# schematic_gprs.net
KiCad netlist of a schematic drawn in EAGLE
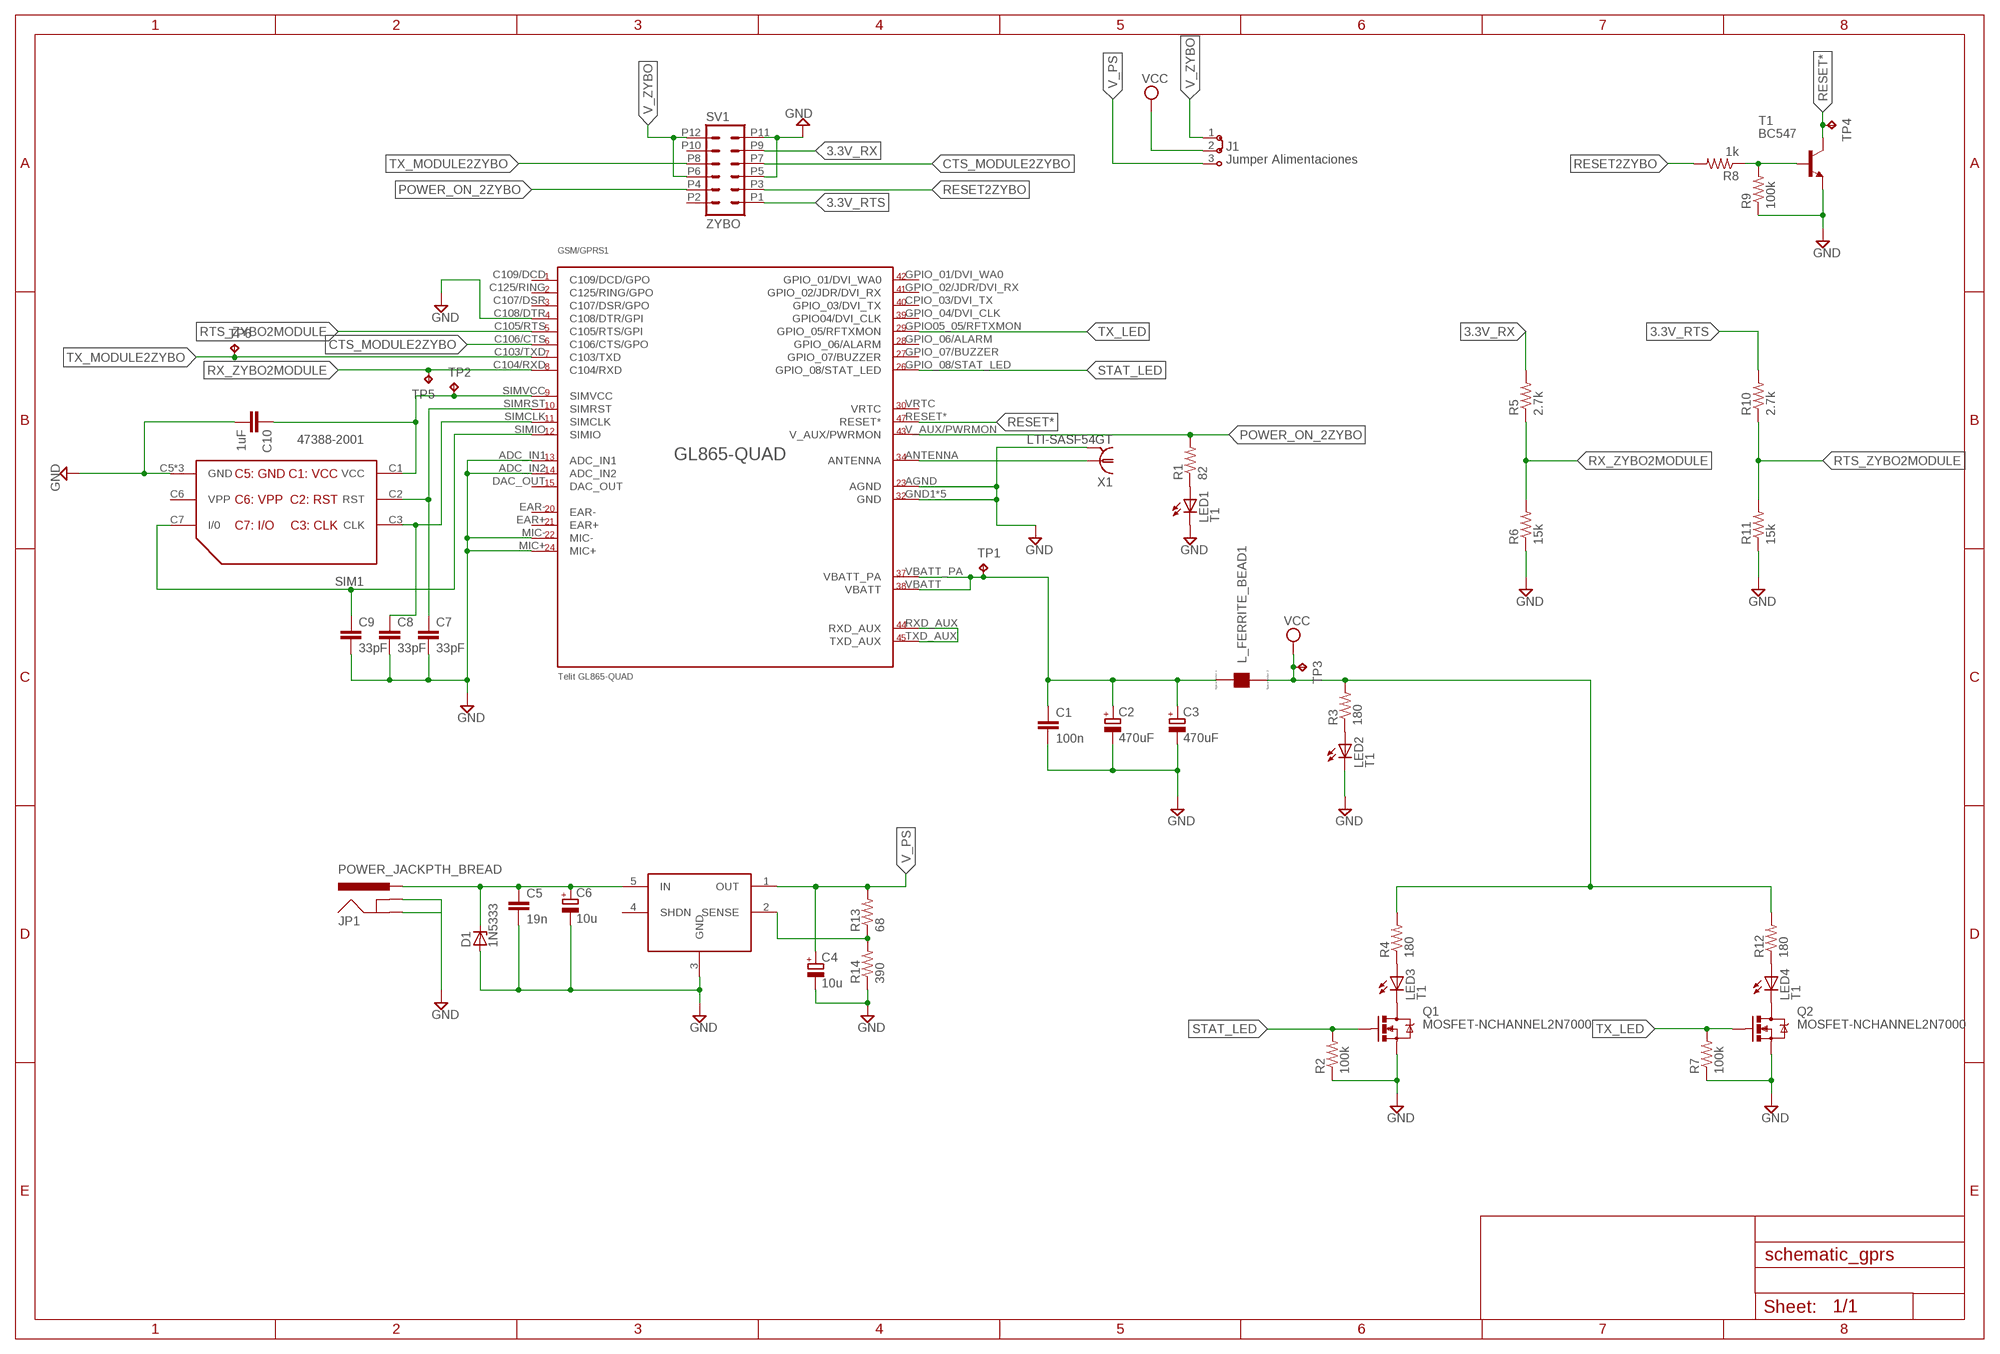
[diagram p0: schematic, sheet 1]

(export (version "E")
  (design (tool "Eeschema 10.0.6"))
  (components
    (comp (ref "C1")
      (value "100n")
      (footprint "eagle-import:C2.5-2")
      (libsource (lib "eagle-import") (part "C2.5/2"))
    )
    (comp (ref "C2")
      (value "470uF")
      (footprint "eagle-import:E3,5-8")
      (libsource (lib "eagle-import") (part "CPOL-EUE3.5-8"))
    )
    (comp (ref "C3")
      (value "470uF")
      (footprint "eagle-import:E3,5-8")
      (libsource (lib "eagle-import") (part "CPOL-EUE3.5-8"))
    )
    (comp (ref "C4")
      (value "10u")
      (footprint "eagle-import:E2-5")
      (libsource (lib "eagle-import") (part "CPOL-EUE2-5"))
    )
    (comp (ref "C5")
      (value "19n")
      (footprint "eagle-import:C050-025X075")
      (libsource (lib "eagle-import") (part "resistor_C-EU050-025X075"))
    )
    (comp (ref "C6")
      (value "10u")
      (footprint "eagle-import:E1,8-4")
      (libsource (lib "eagle-import") (part "CPOL-EUE1.8-4"))
    )
    (comp (ref "C7")
      (value "33pF")
      (footprint "eagle-import:C025-024X044")
      (libsource (lib "eagle-import") (part "C-EU025-024X044"))
    )
    (comp (ref "C8")
      (value "33pF")
      (footprint "eagle-import:C025-024X044")
      (libsource (lib "eagle-import") (part "C-EU025-024X044"))
    )
    (comp (ref "C9")
      (value "33pF")
      (footprint "eagle-import:C025-024X044")
      (libsource (lib "eagle-import") (part "C-EU025-024X044"))
    )
    (comp (ref "C10")
      (value "1uF")
      (footprint "eagle-import:CAP-PTH-SMALL-KIT")
      (libsource (lib "eagle-import") (part "CAPKIT"))
    )
    (comp (ref "D1")
      (value "1N5333")
      (footprint "eagle-import:C1702-15")
      (libsource (lib "eagle-import") (part "1N5333"))
    )
    (comp (ref "GSM/GPRS1")
      (value "Telit GL865-QUAD")
      (footprint "eagle-import:GL865-QUAD")
      (libsource (lib "eagle-import") (part "GL865-QUAD"))
    )
    (comp (ref "J1")
      (value "Jumper Alimentaciones")
      (footprint "eagle-import:04C")
      (libsource (lib "eagle-import") (part "J2X2MM"))
    )
    (comp (ref "JP1")
      (value "POWER_JACKPTH_BREAD")
      (footprint "eagle-import:POWER_JACK_PTH_BREAD")
      (libsource (lib "eagle-import") (part "POWER_JACKPTH_BREAD"))
    )
    (comp (ref "LED1")
      (value "T1")
      (footprint "eagle-import:LED3MM")
      (libsource (lib "eagle-import") (part "LED3MM"))
    )
    (comp (ref "LED2")
      (value "T1")
      (footprint "eagle-import:LED3MM")
      (libsource (lib "eagle-import") (part "LED3MM"))
    )
    (comp (ref "LED3")
      (value "T1")
      (footprint "eagle-import:LED3MM")
      (libsource (lib "eagle-import") (part "LED3MM"))
    )
    (comp (ref "LED4")
      (value "T1")
      (footprint "eagle-import:LED3MM")
      (libsource (lib "eagle-import") (part "LED3MM"))
    )
    (comp (ref "L_FERRITE_BEAD1")
      (value "FERRITEBEAD2")
      (footprint "eagle-import:0207_7")
      (libsource (lib "eagle-import") (part "FERRITEBEAD2"))
    )
    (comp (ref "Q1")
      (value "MOSFET-NCHANNEL2N7000")
      (footprint "eagle-import:TO-92")
      (libsource (lib "eagle-import") (part "MOSFET-NCHANNEL2N7000"))
    )
    (comp (ref "Q2")
      (value "MOSFET-NCHANNEL2N7000")
      (footprint "eagle-import:TO-92")
      (libsource (lib "eagle-import") (part "MOSFET-NCHANNEL2N7000"))
    )
    (comp (ref "R1")
      (value "82")
      (footprint "eagle-import:0207_7")
      (libsource (lib "eagle-import") (part "R-US_0207/7"))
    )
    (comp (ref "R2")
      (value "100k")
      (footprint "eagle-import:0207_7")
      (libsource (lib "eagle-import") (part "R-US_0207/7"))
    )
    (comp (ref "R3")
      (value "180")
      (footprint "eagle-import:0207_7")
      (libsource (lib "eagle-import") (part "R-US_0207/7"))
    )
    (comp (ref "R4")
      (value "180")
      (footprint "eagle-import:0207_7")
      (libsource (lib "eagle-import") (part "R-US_0207/7"))
    )
    (comp (ref "R5")
      (value "2.7k")
      (footprint "eagle-import:0207_7")
      (libsource (lib "eagle-import") (part "R-US_0207/7"))
    )
    (comp (ref "R6")
      (value "15k")
      (footprint "eagle-import:0207_7")
      (libsource (lib "eagle-import") (part "R-US_0207/7"))
    )
    (comp (ref "R7")
      (value "100k")
      (footprint "eagle-import:0207_7")
      (libsource (lib "eagle-import") (part "R-US_0207/7"))
    )
    (comp (ref "R8")
      (value "1k")
      (footprint "eagle-import:0207_7")
      (libsource (lib "eagle-import") (part "R-US_0207/7"))
    )
    (comp (ref "R9")
      (value "100k")
      (footprint "eagle-import:0207_7")
      (libsource (lib "eagle-import") (part "R-US_0207/7"))
    )
    (comp (ref "R10")
      (value "2.7k")
      (footprint "eagle-import:0207_7")
      (libsource (lib "eagle-import") (part "R-US_0207/7"))
    )
    (comp (ref "R11")
      (value "15k")
      (footprint "eagle-import:0207_7")
      (libsource (lib "eagle-import") (part "R-US_0207/7"))
    )
    (comp (ref "R12")
      (value "180")
      (footprint "eagle-import:0207_7")
      (libsource (lib "eagle-import") (part "R-US_0207/7"))
    )
    (comp (ref "R13")
      (value "68")
      (footprint "eagle-import:0207_7")
      (libsource (lib "eagle-import") (part "R-US_0207/7"))
    )
    (comp (ref "R14")
      (value "390")
      (footprint "eagle-import:0207_7")
      (libsource (lib "eagle-import") (part "R-US_0207/7"))
    )
    (comp (ref "SIM1")
      (value "47388-2001")
      (footprint "eagle-import:47388-2001")
      (libsource (lib "eagle-import") (part "47388-2001"))
    )
    (comp (ref "SV1")
      (value "ZYBO")
      (footprint "eagle-import:MA06-2")
      (libsource (lib "eagle-import") (part "MA06-2"))
    )
    (comp (ref "T1")
      (value "BC547")
      (footprint "eagle-import:TO92")
      (libsource (lib "eagle-import") (part "BC547"))
    )
    (comp (ref "TP1")
      (value "TPPAD1-13")
      (footprint "eagle-import:P1-13")
      (libsource (lib "eagle-import") (part "TPPAD1-13"))
    )
    (comp (ref "TP2")
      (value "TPPAD1-13")
      (footprint "eagle-import:P1-13")
      (libsource (lib "eagle-import") (part "TPPAD1-13"))
    )
    (comp (ref "TP3")
      (value "TPPAD1-13")
      (footprint "eagle-import:P1-13")
      (libsource (lib "eagle-import") (part "TPPAD1-13"))
    )
    (comp (ref "TP4")
      (value "TPPAD1-13")
      (footprint "eagle-import:P1-13")
      (libsource (lib "eagle-import") (part "TPPAD1-13"))
    )
    (comp (ref "TP5")
      (value "TPPAD1-13")
      (footprint "eagle-import:P1-13")
      (libsource (lib "eagle-import") (part "TPPAD1-13"))
    )
    (comp (ref "TP6")
      (value "TPPAD1-13")
      (footprint "eagle-import:P1-13")
      (libsource (lib "eagle-import") (part "TPPAD1-13"))
    )
    (comp (ref "U$1")
      (value "LT1528")
      (footprint "eagle-import:Q5-DD")
      (libsource (lib "eagle-import") (part "LT1528"))
    )
    (comp (ref "X1")
      (value "LTI-SASF54GT")
      (footprint "eagle-import:LTI-SASF54GT")
      (libsource (lib "eagle-import") (part "LTI-SASF54GT"))
    )
  )
  (nets
    (net (code "1") (name "3.3V_RTS") (class "Default")
      (node (ref "R10") (pin "2") (pinfunction "2_2") (pintype "passive"))
      (node (ref "SV1") (pin "P1") (pinfunction "1_P1") (pintype "passive"))
    )
    (net (code "2") (name "3.3V_RX") (class "Default")
      (node (ref "R5") (pin "2") (pinfunction "2_2") (pintype "passive"))
      (node (ref "SV1") (pin "P9") (pinfunction "9_P9") (pintype "passive"))
    )
    (net (code "3") (name "CTS_MODULE2ZYBO") (class "Default")
      (node (ref "GSM/GPRS1") (pin "C106/CTS") (pinfunction "C106/CTS/GPO_C106/CTS") (pintype "output"))
      (node (ref "SV1") (pin "P7") (pinfunction "7_P7") (pintype "passive"))
    )
    (net (code "4") (name "GND") (class "Default")
      (node (ref "C1") (pin "2") (pinfunction "2_2") (pintype "passive"))
      (node (ref "C10") (pin "2") (pinfunction "2_2") (pintype "passive"))
      (node (ref "C2") (pin "-") (pinfunction "-_-") (pintype "passive"))
      (node (ref "C3") (pin "-") (pinfunction "-_-") (pintype "passive"))
      (node (ref "C4") (pin "-") (pinfunction "-_-") (pintype "passive"))
      (node (ref "C5") (pin "2") (pinfunction "2_2") (pintype "passive"))
      (node (ref "C6") (pin "-") (pinfunction "-_-") (pintype "passive"))
      (node (ref "C7") (pin "2") (pinfunction "2_2") (pintype "passive"))
      (node (ref "C8") (pin "2") (pinfunction "2_2") (pintype "passive"))
      (node (ref "C9") (pin "2") (pinfunction "2_2") (pintype "passive"))
      (node (ref "D1") (pin "A") (pinfunction "A_A") (pintype "passive"))
      (node (ref "GSM/GPRS1") (pin "ADC_IN1") (pinfunction "ADC_IN1_ADC_IN1") (pintype "input"))
      (node (ref "GSM/GPRS1") (pin "ADC_IN2") (pinfunction "ADC_IN2_ADC_IN2") (pintype "input"))
      (node (ref "GSM/GPRS1") (pin "AGND") (pinfunction "AGND_AGND") (pintype "power_in"))
      (node (ref "GSM/GPRS1") (pin "C108/DTR") (pinfunction "C108/DTR/GPI_C108/DTR") (pintype "input"))
      (node (ref "GSM/GPRS1") (pin "GND1") (pinfunction "GND_GND1") (pintype "power_in"))
      (node (ref "GSM/GPRS1") (pin "GND2") (pinfunction "GND_GND2") (pintype "power_in"))
      (node (ref "GSM/GPRS1") (pin "GND3") (pinfunction "GND_GND3") (pintype "power_in"))
      (node (ref "GSM/GPRS1") (pin "GND4") (pinfunction "GND_GND4") (pintype "power_in"))
      (node (ref "GSM/GPRS1") (pin "GND5") (pinfunction "GND_GND5") (pintype "power_in"))
      (node (ref "GSM/GPRS1") (pin "MIC+") (pinfunction "MIC+_MIC+") (pintype "input"))
      (node (ref "GSM/GPRS1") (pin "MIC-") (pinfunction "MIC-_MIC-") (pintype "input"))
      (node (ref "JP1") (pin "GND") (pinfunction "GND_GND") (pintype "bidirectional"))
      (node (ref "JP1") (pin "GNDBREAK") (pinfunction "GNDBREAK_GNDBREAK") (pintype "bidirectional"))
      (node (ref "LED1") (pin "K") (pinfunction "C_K") (pintype "passive"))
      (node (ref "LED2") (pin "K") (pinfunction "C_K") (pintype "passive"))
      (node (ref "Q1") (pin "1") (pinfunction "S_1") (pintype "passive"))
      (node (ref "Q2") (pin "1") (pinfunction "S_1") (pintype "passive"))
      (node (ref "R11") (pin "1") (pinfunction "1_1") (pintype "passive"))
      (node (ref "R14") (pin "1") (pinfunction "1_1") (pintype "passive"))
      (node (ref "R2") (pin "1") (pinfunction "1_1") (pintype "passive"))
      (node (ref "R6") (pin "1") (pinfunction "1_1") (pintype "passive"))
      (node (ref "R7") (pin "1") (pinfunction "1_1") (pintype "passive"))
      (node (ref "R9") (pin "1") (pinfunction "1_1") (pintype "passive"))
      (node (ref "SIM1") (pin "C5") (pinfunction "GND_C5") (pintype "power_in"))
      (node (ref "SIM1") (pin "GND1") (pinfunction "GND_GND1") (pintype "power_in"))
      (node (ref "SIM1") (pin "GND2") (pinfunction "GND_GND2") (pintype "power_in"))
      (node (ref "SV1") (pin "P11") (pinfunction "11_P11") (pintype "passive"))
      (node (ref "SV1") (pin "P5") (pinfunction "5_P5") (pintype "passive"))
      (node (ref "T1") (pin "1") (pinfunction "E_1") (pintype "passive"))
      (node (ref "U$1") (pin "3") (pinfunction "GND_3") (pintype "bidirectional"))
      (node (ref "X1") (pin "2") (pinfunction "2_2") (pintype "passive"))
      (node (ref "X1") (pin "3") (pinfunction "2_3") (pintype "passive"))
      (node (ref "X1") (pin "4") (pinfunction "2_4") (pintype "passive"))
      (node (ref "X1") (pin "5") (pinfunction "2_5") (pintype "passive"))
    )
    (net (code "5") (name "Net-(GSM/GPRS1-PadANTENNA)") (class "Default")
      (node (ref "GSM/GPRS1") (pin "ANTENNA") (pinfunction "ANTENNA_ANTENNA") (pintype "output"))
      (node (ref "X1") (pin "1") (pinfunction "1_1") (pintype "passive"))
    )
    (net (code "6") (name "Net-(GSM/GPRS1-PadRXD_AUX)") (class "Default")
      (node (ref "GSM/GPRS1") (pin "RXD_AUX") (pinfunction "RXD_AUX_RXD_AUX") (pintype "input"))
      (node (ref "GSM/GPRS1") (pin "TXD_AUX") (pinfunction "TXD_AUX_TXD_AUX") (pintype "output"))
    )
    (net (code "7") (name "Net-(LED1-PadA)") (class "Default")
      (node (ref "LED1") (pin "A") (pinfunction "A_A") (pintype "passive"))
      (node (ref "R1") (pin "1") (pinfunction "1_1") (pintype "passive"))
    )
    (net (code "8") (name "Net-(LED2-PadA)") (class "Default")
      (node (ref "LED2") (pin "A") (pinfunction "A_A") (pintype "passive"))
      (node (ref "R3") (pin "1") (pinfunction "1_1") (pintype "passive"))
    )
    (net (code "9") (name "Net-(LED3-C)") (class "Default")
      (node (ref "LED3") (pin "K") (pinfunction "C_K") (pintype "passive"))
      (node (ref "Q1") (pin "3") (pinfunction "D_3") (pintype "passive"))
    )
    (net (code "10") (name "Net-(LED3-PadA)") (class "Default")
      (node (ref "LED3") (pin "A") (pinfunction "A_A") (pintype "passive"))
      (node (ref "R4") (pin "1") (pinfunction "1_1") (pintype "passive"))
    )
    (net (code "11") (name "Net-(LED4-C)") (class "Default")
      (node (ref "LED4") (pin "K") (pinfunction "C_K") (pintype "passive"))
      (node (ref "Q2") (pin "3") (pinfunction "D_3") (pintype "passive"))
    )
    (net (code "12") (name "Net-(LED4-PadA)") (class "Default")
      (node (ref "LED4") (pin "A") (pinfunction "A_A") (pintype "passive"))
      (node (ref "R12") (pin "1") (pinfunction "1_1") (pintype "passive"))
    )
    (net (code "13") (name "Net-(L_FERRITE_BEAD1-A)") (class "Default")
      (node (ref "C1") (pin "1") (pinfunction "1_1") (pintype "passive"))
      (node (ref "C2") (pin "+") (pinfunction "+_+") (pintype "passive"))
      (node (ref "C3") (pin "+") (pinfunction "+_+") (pintype "passive"))
      (node (ref "GSM/GPRS1") (pin "VBATT") (pinfunction "VBATT_VBATT") (pintype "power_in"))
      (node (ref "GSM/GPRS1") (pin "VBATT_PA") (pinfunction "VBATT_PA_VBATT_PA") (pintype "power_in"))
      (node (ref "L_FERRITE_BEAD1") (pin "1") (pinfunction "A_1") (pintype "passive"))
      (node (ref "TP1") (pin "TP") (pinfunction "TP_TP") (pintype "input"))
    )
    (net (code "14") (name "Net-(SIM1-CLK)") (class "Default")
      (node (ref "C8") (pin "1") (pinfunction "1_1") (pintype "passive"))
      (node (ref "GSM/GPRS1") (pin "SIMCLK") (pinfunction "SIMCLK_SIMCLK") (pintype "output"))
      (node (ref "SIM1") (pin "C3") (pinfunction "CLK_C3") (pintype "input"))
    )
    (net (code "15") (name "Net-(SIM1-I{slash}0)") (class "Default")
      (node (ref "C9") (pin "1") (pinfunction "1_1") (pintype "passive"))
      (node (ref "GSM/GPRS1") (pin "SIMIO") (pinfunction "SIMIO_SIMIO") (pintype "bidirectional"))
      (node (ref "SIM1") (pin "C7") (pinfunction "I/0_C7") (pintype "bidirectional"))
    )
    (net (code "16") (name "Net-(SIM1-RST)") (class "Default")
      (node (ref "C7") (pin "1") (pinfunction "1_1") (pintype "passive"))
      (node (ref "GSM/GPRS1") (pin "SIMRST") (pinfunction "SIMRST_SIMRST") (pintype "output"))
      (node (ref "SIM1") (pin "C2") (pinfunction "RST_C2") (pintype "input"))
    )
    (net (code "17") (name "Net-(SIM1-VCC)") (class "Default")
      (node (ref "C10") (pin "1") (pinfunction "1_1") (pintype "passive"))
      (node (ref "GSM/GPRS1") (pin "SIMVCC") (pinfunction "SIMVCC_SIMVCC") (pintype "power_in"))
      (node (ref "SIM1") (pin "C1") (pinfunction "VCC_C1") (pintype "power_in"))
      (node (ref "TP2") (pin "TP") (pinfunction "TP_TP") (pintype "input"))
    )
    (net (code "18") (name "Net-(T1-B)") (class "Default")
      (node (ref "R8") (pin "1") (pinfunction "1_1") (pintype "passive"))
      (node (ref "R9") (pin "2") (pinfunction "2_2") (pintype "passive"))
      (node (ref "T1") (pin "2") (pinfunction "B_2") (pintype "passive"))
    )
    (net (code "19") (name "Net-(U$1-IN)") (class "Default")
      (node (ref "C5") (pin "1") (pinfunction "1_1") (pintype "passive"))
      (node (ref "C6") (pin "+") (pinfunction "+_+") (pintype "passive"))
      (node (ref "D1") (pin "C") (pinfunction "C_C") (pintype "passive"))
      (node (ref "JP1") (pin "PWR") (pinfunction "PWR_PWR") (pintype "bidirectional"))
      (node (ref "U$1") (pin "5") (pinfunction "IN_5") (pintype "bidirectional"))
    )
    (net (code "20") (name "Net-(U$1-SENSE)") (class "Default")
      (node (ref "R13") (pin "1") (pinfunction "1_1") (pintype "passive"))
      (node (ref "R14") (pin "2") (pinfunction "2_2") (pintype "passive"))
      (node (ref "U$1") (pin "2") (pinfunction "SENSE_2") (pintype "bidirectional"))
    )
    (net (code "21") (name "POWER_ON_2ZYBO") (class "Default")
      (node (ref "GSM/GPRS1") (pin "V_AUX/PWRMON") (pinfunction "V_AUX/PWRMON_V_AUX/PWRMON") (pintype "output"))
      (node (ref "R1") (pin "2") (pinfunction "2_2") (pintype "passive"))
      (node (ref "SV1") (pin "P4") (pinfunction "4_P4") (pintype "passive"))
    )
    (net (code "22") (name "RESET*") (class "Default")
      (node (ref "GSM/GPRS1") (pin "RESET*") (pinfunction "RESET*_RESET*") (pintype "input"))
      (node (ref "T1") (pin "3") (pinfunction "C_3") (pintype "passive"))
      (node (ref "TP4") (pin "TP") (pinfunction "TP_TP") (pintype "input"))
    )
    (net (code "23") (name "RESET2ZYBO") (class "Default")
      (node (ref "R8") (pin "2") (pinfunction "2_2") (pintype "passive"))
      (node (ref "SV1") (pin "P3") (pinfunction "3_P3") (pintype "passive"))
    )
    (net (code "24") (name "RTS_ZYBO2MODULE") (class "Default")
      (node (ref "GSM/GPRS1") (pin "C105/RTS") (pinfunction "C105/RTS/GPI_C105/RTS") (pintype "input"))
      (node (ref "R10") (pin "1") (pinfunction "1_1") (pintype "passive"))
      (node (ref "R11") (pin "2") (pinfunction "2_2") (pintype "passive"))
    )
    (net (code "25") (name "RX_ZYBO2MODULE") (class "Default")
      (node (ref "GSM/GPRS1") (pin "C104/RXD") (pinfunction "C104/RXD_C104/RXD") (pintype "output"))
      (node (ref "R5") (pin "1") (pinfunction "1_1") (pintype "passive"))
      (node (ref "R6") (pin "2") (pinfunction "2_2") (pintype "passive"))
      (node (ref "TP5") (pin "TP") (pinfunction "TP_TP") (pintype "input"))
    )
    (net (code "26") (name "STAT_LED") (class "Default")
      (node (ref "GSM/GPRS1") (pin "GPIO_08/STAT_LED") (pinfunction "GPIO_08/STAT_LED_GPIO_08/STAT_LED") (pintype "bidirectional"))
      (node (ref "Q1") (pin "2") (pinfunction "G_2") (pintype "passive"))
      (node (ref "R2") (pin "2") (pinfunction "2_2") (pintype "passive"))
    )
    (net (code "27") (name "TX_LED") (class "Default")
      (node (ref "GSM/GPRS1") (pin "GPIO05_05/RFTXMON") (pinfunction "GPIO_05/RFTXMON_GPIO05_05/RFTXMON") (pintype "bidirectional"))
      (node (ref "Q2") (pin "2") (pinfunction "G_2") (pintype "passive"))
      (node (ref "R7") (pin "2") (pinfunction "2_2") (pintype "passive"))
    )
    (net (code "28") (name "TX_MODULE2ZYBO") (class "Default")
      (node (ref "GSM/GPRS1") (pin "C103/TXD") (pinfunction "C103/TXD_C103/TXD") (pintype "input"))
      (node (ref "SV1") (pin "P8") (pinfunction "8_P8") (pintype "passive"))
      (node (ref "TP6") (pin "TP") (pinfunction "TP_TP") (pintype "input"))
    )
    (net (code "29") (name "VCC") (class "Default")
      (node (ref "J1") (pin "2") (pinfunction "2_2") (pintype "passive"))
      (node (ref "L_FERRITE_BEAD1") (pin "2") (pinfunction "B_2") (pintype "passive"))
      (node (ref "R12") (pin "2") (pinfunction "2_2") (pintype "passive"))
      (node (ref "R3") (pin "2") (pinfunction "2_2") (pintype "passive"))
      (node (ref "R4") (pin "2") (pinfunction "2_2") (pintype "passive"))
      (node (ref "TP3") (pin "TP") (pinfunction "TP_TP") (pintype "input"))
    )
    (net (code "30") (name "V_PS") (class "Default")
      (node (ref "C4") (pin "+") (pinfunction "+_+") (pintype "passive"))
      (node (ref "J1") (pin "3") (pinfunction "3_3") (pintype "passive"))
      (node (ref "R13") (pin "2") (pinfunction "2_2") (pintype "passive"))
      (node (ref "U$1") (pin "1") (pinfunction "OUT_1") (pintype "bidirectional"))
    )
    (net (code "31") (name "V_ZYBO") (class "Default")
      (node (ref "J1") (pin "1") (pinfunction "1_1") (pintype "passive"))
      (node (ref "SV1") (pin "P12") (pinfunction "12_P12") (pintype "passive"))
      (node (ref "SV1") (pin "P6") (pinfunction "6_P6") (pintype "passive"))
    )
    (net (code "32") (name "unconnected-(GSM/GPRS1-C107{slash}DSR{slash}GPO-PadC107{slash}DSR)") (class "Default")
      (node (ref "GSM/GPRS1") (pin "C107/DSR") (pinfunction "C107/DSR/GPO_C107/DSR") (pintype "output"))
    )
    (net (code "33") (name "unconnected-(GSM/GPRS1-C109{slash}DCD{slash}GPO-PadC109{slash}DCD)") (class "Default")
      (node (ref "GSM/GPRS1") (pin "C109/DCD") (pinfunction "C109/DCD/GPO_C109/DCD") (pintype "output"))
    )
    (net (code "34") (name "unconnected-(GSM/GPRS1-C125{slash}RING{slash}GPO-PadC125{slash}RING)") (class "Default")
      (node (ref "GSM/GPRS1") (pin "C125/RING") (pinfunction "C125/RING/GPO_C125/RING") (pintype "output"))
    )
    (net (code "35") (name "unconnected-(GSM/GPRS1-GPIO04{slash}DVI_CLK-PadGPIO_04{slash}DVI_CLK)") (class "Default")
      (node (ref "GSM/GPRS1") (pin "GPIO_04/DVI_CLK") (pinfunction "GPIO04/DVI_CLK_GPIO_04/DVI_CLK") (pintype "bidirectional"))
    )
    (net (code "36") (name "unconnected-(GSM/GPRS1-GPIO_03{slash}DVI_TX-PadCPIO_03{slash}DVI_TX)") (class "Default")
      (node (ref "GSM/GPRS1") (pin "CPIO_03/DVI_TX") (pinfunction "GPIO_03/DVI_TX_CPIO_03/DVI_TX") (pintype "bidirectional"))
    )
    (net (code "37") (name "unconnected-(GSM/GPRS1-PadDAC_OUT)") (class "Default")
      (node (ref "GSM/GPRS1") (pin "DAC_OUT") (pinfunction "DAC_OUT_DAC_OUT") (pintype "output"))
    )
    (net (code "38") (name "unconnected-(GSM/GPRS1-PadEAR+)") (class "Default")
      (node (ref "GSM/GPRS1") (pin "EAR+") (pinfunction "EAR+_EAR+") (pintype "output"))
    )
    (net (code "39") (name "unconnected-(GSM/GPRS1-PadEAR-)") (class "Default")
      (node (ref "GSM/GPRS1") (pin "EAR-") (pinfunction "EAR-_EAR-") (pintype "output"))
    )
    (net (code "40") (name "unconnected-(GSM/GPRS1-PadGPIO_01{slash}DVI_WA0)") (class "Default")
      (node (ref "GSM/GPRS1") (pin "GPIO_01/DVI_WA0") (pinfunction "GPIO_01/DVI_WA0_GPIO_01/DVI_WA0") (pintype "bidirectional"))
    )
    (net (code "41") (name "unconnected-(GSM/GPRS1-PadGPIO_02{slash}JDR{slash}DVI_RX)") (class "Default")
      (node (ref "GSM/GPRS1") (pin "GPIO_02/JDR/DVI_RX") (pinfunction "GPIO_02/JDR/DVI_RX_GPIO_02/JDR/DVI_RX") (pintype "bidirectional"))
    )
    (net (code "42") (name "unconnected-(GSM/GPRS1-PadGPIO_06{slash}ALARM)") (class "Default")
      (node (ref "GSM/GPRS1") (pin "GPIO_06/ALARM") (pinfunction "GPIO_06/ALARM_GPIO_06/ALARM") (pintype "bidirectional"))
    )
    (net (code "43") (name "unconnected-(GSM/GPRS1-PadGPIO_07{slash}BUZZER)") (class "Default")
      (node (ref "GSM/GPRS1") (pin "GPIO_07/BUZZER") (pinfunction "GPIO_07/BUZZER_GPIO_07/BUZZER") (pintype "bidirectional"))
    )
    (net (code "44") (name "unconnected-(GSM/GPRS1-PadVRTC)") (class "Default")
      (node (ref "GSM/GPRS1") (pin "VRTC") (pinfunction "VRTC_VRTC") (pintype "output"))
    )
    (net (code "45") (name "unconnected-(SIM1-VPP-PadC6)") (class "Default")
      (node (ref "SIM1") (pin "C6") (pinfunction "VPP_C6") (pintype "bidirectional"))
    )
    (net (code "46") (name "unconnected-(SV1-2-PadP2)") (class "Default")
      (node (ref "SV1") (pin "P2") (pinfunction "2_P2") (pintype "passive"))
    )
    (net (code "47") (name "unconnected-(SV1-10-PadP10)") (class "Default")
      (node (ref "SV1") (pin "P10") (pinfunction "10_P10") (pintype "passive"))
    )
    (net (code "48") (name "unconnected-(U$1-SHDN-Pad4)") (class "Default")
      (node (ref "U$1") (pin "4") (pinfunction "SHDN_4") (pintype "bidirectional"))
    )
  )
)
